# IO_MIL1553_TopConfiguration.net
KiCad netlist of a schematic drawn in Altium Designer
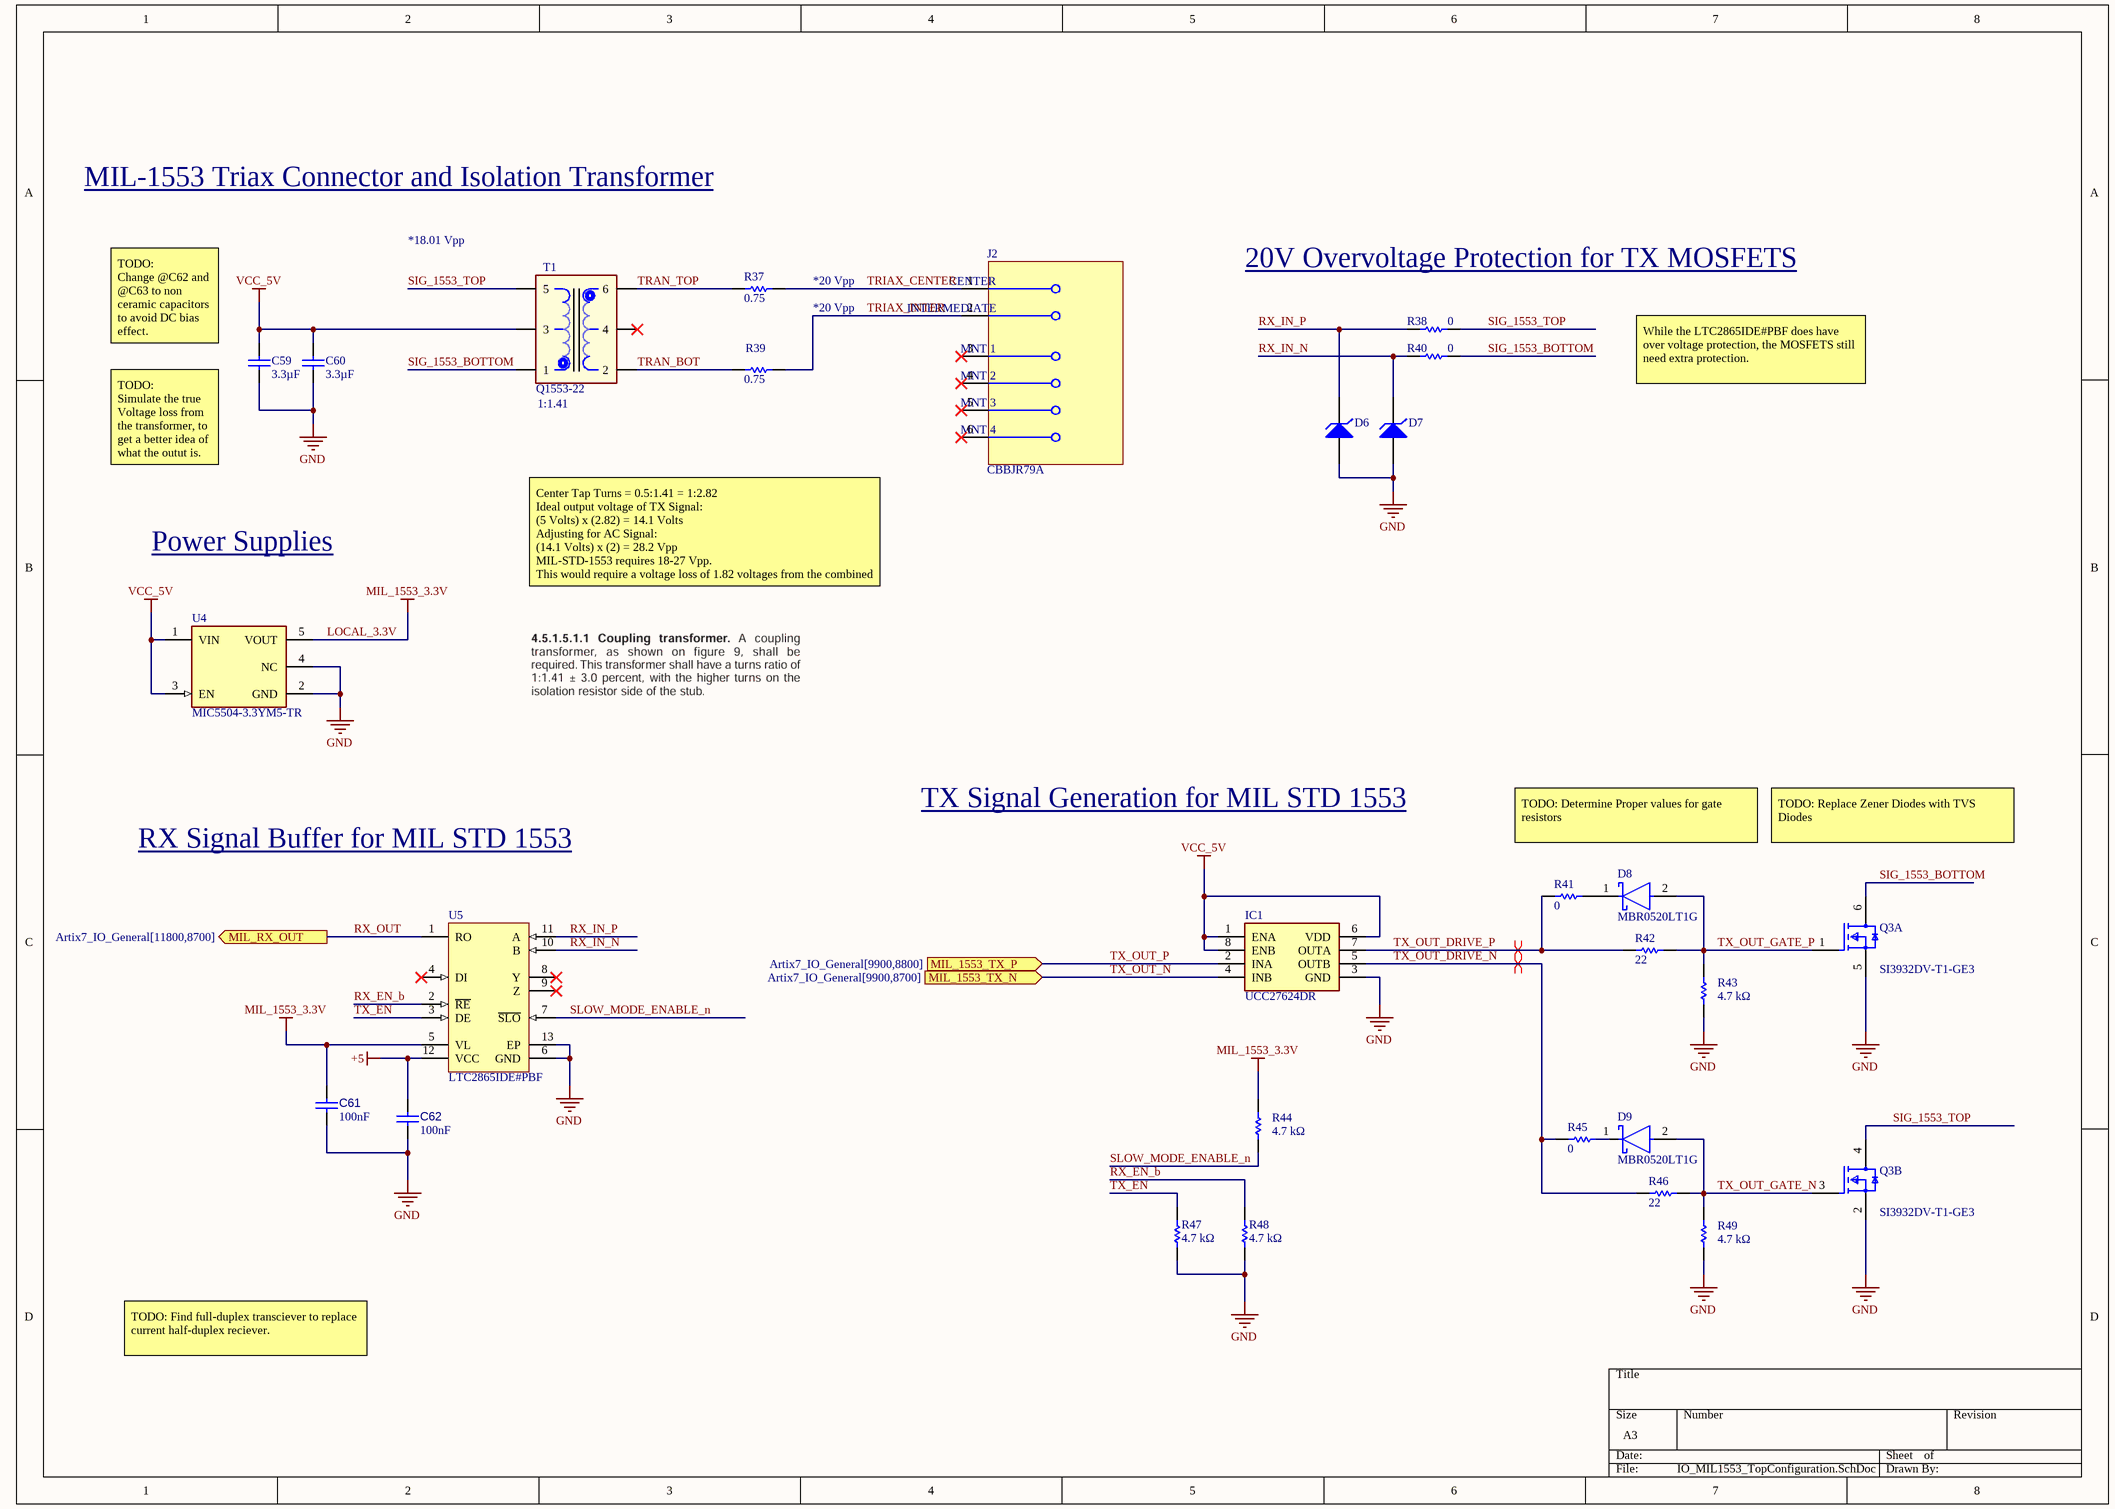
[diagram p0: IO_MIL1553_TopConfiguration.SchDoc]

(export (version "E")
  (design (tool "Eeschema 10.0.6"))
  (components
    (comp (ref "C59")
      (value "3.3µF")
      (footprint "CAPC3325X279X50NL40T25")
      (fields (field (name "Comment") "12105C335KAT2A"))
      (libsource (lib "Personal Workspace") (part "CAP-NP-2"))
    )
    (comp (ref "C60")
      (value "3.3µF")
      (footprint "CAPC3325X279X50NL40T25")
      (fields (field (name "Comment") "12105C335KAT2A"))
      (libsource (lib "Personal Workspace") (part "CAP-NP-2"))
    )
    (comp (ref "C61")
      (value "100nF")
      (footprint "CAPC2013X145X48ML20T23")
      (fields (field (name "Comment") "VJ0805Y104JXXAT"))
      (libsource (lib "Personal Workspace") (part "CAP-NP-2"))
    )
    (comp (ref "C62")
      (value "100nF")
      (footprint "CAPC2013X145X48ML20T23")
      (fields (field (name "Comment") "VJ0805Y104JXXAT"))
      (libsource (lib "Personal Workspace") (part "CAP-NP-2"))
    )
    (comp (ref "D6")
      (value "SZ1SMA5932BT3G")
      (footprint "ONSC-SMA-2-403D-02_F_V")
      (description "Zener Diode, 20V V(Z), 5%, 0.5W, Silicon, Unidirectional")
      (libsource (lib "Personal Workspace") (part "ONSC-K1A2-2"))
    )
    (comp (ref "D7")
      (value "SZ1SMA5932BT3G")
      (footprint "ONSC-SMA-2-403D-02_F_V")
      (description "Zener Diode, 20V V(Z), 5%, 0.5W, Silicon, Unidirectional")
      (libsource (lib "Personal Workspace") (part "ONSC-K1A2-2"))
    )
    (comp (ref "D8")
      (value "MBR0520LT1G")
      (footprint "FP-425-04-IPC_A")
      (description "Rectifier Diode, Schottky, 1 Phase, 1 Element, 0.5A, 20V V(RRM), Silicon")
      (libsource (lib "Personal Workspace") (part "1d6ec82d83fb6aee721767c19dac4b9"))
    )
    (comp (ref "D9")
      (value "MBR0520LT1G")
      (footprint "FP-425-04-IPC_A")
      (description "Rectifier Diode, Schottky, 1 Phase, 1 Element, 0.5A, 20V V(RRM), Silicon")
      (libsource (lib "Personal Workspace") (part "1d6ec82d83fb6aee721767c19dac4b9"))
    )
    (comp (ref "IC1")
      (value "UCC27624DR")
      (footprint "SamacSys:SOIC127P600X175-8N")
      (description "Integrated Circuit")
      (fields (field (name "MOUSER PART NUMBER") "595-UCC27624DR"))
      (libsource (lib "*") (part "UCC27624DR"))
    )
    (comp (ref "J2")
      (value "CBBJR79A")
      (footprint "CBBJR79A_MFG")
      (description "RF Triaxial-BNC Connector, Female, Panel Mount, Board And Panel Mount, Solder Terminal, Jack")
      (libsource (lib "Altium Content Vault") (part "f0f2aa2fa52ada01177f191ae970a7c"))
    )
    (comp (ref "Q3")
      (value "SI3932DV-T1-GE3")
      (footprint "FP-C-06593-6-IPC_B")
      (libsource (lib "Personal Workspace") (part "c257f011501cba683afc6ad259169fc"))
    )
    (comp (ref "R37")
      (value "0.75")
      (footprint "RESC3125X70X40LL20T20")
      (fields
        (field (name "POWER") "1W")
        (field (name "TOLERANCE") "1%")
        (field (name "Comment") "RES_0.75ohm_1W _1210")
      )
      (libsource (lib "Personal Workspace") (part "RES-2"))
    )
    (comp (ref "R38")
      (value "0")
      (footprint "RESC1608X55X25ML10T15")
      (description "Chip Resistor, 0 Ohm, 0.1 W, -55 to 155 degC, 0603 (1608 Metric)")
      (fields (field (name "POWER") "100mW") (field (name "TOLERANCE") "5%"))
      (libsource (lib "Personal Workspace") (part "RES-2"))
    )
    (comp (ref "R39")
      (value "0.75")
      (footprint "RESC3125X70X40LL20T20")
      (fields
        (field (name "POWER") "1W")
        (field (name "TOLERANCE") "1%")
        (field (name "Comment") "RES_0.75ohm_1W _1210")
      )
      (libsource (lib "Personal Workspace") (part "RES-2"))
    )
    (comp (ref "R40")
      (value "0")
      (footprint "RESC1608X55X25ML10T15")
      (description "Chip Resistor, 0 Ohm, 0.1 W, -55 to 155 degC, 0603 (1608 Metric)")
      (fields (field (name "POWER") "100mW") (field (name "TOLERANCE") "5%"))
      (libsource (lib "Personal Workspace") (part "RES-2"))
    )
    (comp (ref "R41")
      (value "0")
      (footprint "RESC1608X55X25ML10T15")
      (description "Chip Resistor, 0 Ohm, 0.1 W, -55 to 155 degC, 0603 (1608 Metric)")
      (fields (field (name "POWER") "100mW") (field (name "TOLERANCE") "5%"))
      (libsource (lib "Personal Workspace") (part "RES-2"))
    )
    (comp (ref "R42")
      (value "22")
      (footprint "RESC1608X55X25LL10T15")
      (fields
        (field (name "TOLERANCE") "1%")
        (field (name "POWER") "100mW")
        (field (name "Comment") "RC0603FR-0722RL")
      )
      (libsource (lib "Personal Workspace") (part "RES-2"))
    )
    (comp (ref "R43")
      (value "ERJ-3EKF4701V")
      (footprint "RESC1608X55X30LL15T15")
      (fields
        (field (name "TOLERANCE") "1%")
        (field (name "POWER") "100mW")
        (field (name "RESISTANCE") "4.7 kΩ")
      )
      (libsource (lib "Personal Workspace") (part "RES-2"))
    )
    (comp (ref "R44")
      (value "ERJ-3EKF4701V")
      (footprint "RESC1608X55X30LL15T15")
      (fields
        (field (name "TOLERANCE") "1%")
        (field (name "POWER") "100mW")
        (field (name "RESISTANCE") "4.7 kΩ")
      )
      (libsource (lib "Personal Workspace") (part "RES-2"))
    )
    (comp (ref "R45")
      (value "0")
      (footprint "RESC1608X55X25ML10T15")
      (description "Chip Resistor, 0 Ohm, 0.1 W, -55 to 155 degC, 0603 (1608 Metric)")
      (fields (field (name "POWER") "100mW") (field (name "TOLERANCE") "5%"))
      (libsource (lib "Personal Workspace") (part "RES-2"))
    )
    (comp (ref "R46")
      (value "22")
      (footprint "RESC1608X55X25LL10T15")
      (fields
        (field (name "TOLERANCE") "1%")
        (field (name "POWER") "100mW")
        (field (name "Comment") "RC0603FR-0722RL")
      )
      (libsource (lib "Personal Workspace") (part "RES-2"))
    )
    (comp (ref "R47")
      (value "ERJ-3EKF4701V")
      (footprint "RESC1608X55X30LL15T15")
      (fields
        (field (name "TOLERANCE") "1%")
        (field (name "POWER") "100mW")
        (field (name "RESISTANCE") "4.7 kΩ")
      )
      (libsource (lib "Personal Workspace") (part "RES-2"))
    )
    (comp (ref "R48")
      (value "ERJ-3EKF4701V")
      (footprint "RESC1608X55X30LL15T15")
      (fields
        (field (name "TOLERANCE") "1%")
        (field (name "POWER") "100mW")
        (field (name "RESISTANCE") "4.7 kΩ")
      )
      (libsource (lib "Personal Workspace") (part "RES-2"))
    )
    (comp (ref "R49")
      (value "ERJ-3EKF4701V")
      (footprint "RESC1608X55X30LL15T15")
      (fields
        (field (name "TOLERANCE") "1%")
        (field (name "POWER") "100mW")
        (field (name "RESISTANCE") "4.7 kΩ")
      )
      (libsource (lib "Personal Workspace") (part "RES-2"))
    )
    (comp (ref "T1")
      (value "Q1553-22")
      (footprint "New footprint 1")
      (description "Pulse Transformer, GENERAL PURPOSE Application(s), 1CT:1.41CT")
      (fields (field (name "TURNS RATIO") "1:1.41"))
      (libsource (lib "Personal Workspace") (part "Copy of TFORM-4"))
    )
    (comp (ref "U4")
      (value "MIC5504-3.3YM5-TR")
      (footprint "FP-SOT23-5LD-PL-1-MFG")
      (description "IC REG LINEAR 3.3V 300MA SOT23-5")
      (libsource (lib "Altium Content Vault") (part "96048095611b4a9579e1e315950d302"))
    )
    (comp (ref "U5")
      (value "LTC2865IDE#PBF")
      (footprint "LT-DE-UE-12_V")
      (description "Line Transceiver, 1 Func, 1 Driver, 1 Rcvr, CMOS, PDSO12")
      (libsource (lib "Personal Workspace") (part "LT-LTC2865-12"))
    )
  )
  (nets
    (net (code "1") (name "+5") (class "Default")
      (node (ref "C62") (pin "2") (pinfunction "2_2") (pintype "passive"))
      (node (ref "U5") (pin "12") (pinfunction "VCC_12") (pintype "power_in"))
    )
    (net (code "2") (name "/RX_EN_b") (class "Default")
      (node (ref "R48") (pin "1") (pinfunction "1_1") (pintype "passive"))
      (node (ref "U5") (pin "2") (pinfunction "~{RE}_2") (pintype "input"))
    )
    (net (code "3") (name "/RX_IN_N") (class "Default")
      (node (ref "D7") (pin "1") (pinfunction "K_1") (pintype "passive"))
      (node (ref "R40") (pin "1") (pinfunction "1_1") (pintype "passive"))
      (node (ref "U5") (pin "10") (pinfunction "B_10") (pintype "input"))
    )
    (net (code "4") (name "/RX_IN_P") (class "Default")
      (node (ref "D6") (pin "1") (pinfunction "K_1") (pintype "passive"))
      (node (ref "R38") (pin "1") (pinfunction "1_1") (pintype "passive"))
      (node (ref "U5") (pin "11") (pinfunction "A_11") (pintype "input"))
    )
    (net (code "5") (name "/RX_OUT") (class "Default")
      (node (ref "U5") (pin "1") (pinfunction "RO_1") (pintype "tri_state"))
    )
    (net (code "6") (name "/SIG_1553_BOTTOM") (class "Default")
      (node (ref "Q3") (pin "6") (pinfunction "D1_6") (pintype "passive"))
      (node (ref "R40") (pin "2") (pinfunction "2_2") (pintype "passive"))
      (node (ref "T1") (pin "1") (pinfunction "1_1") (pintype "passive"))
    )
    (net (code "7") (name "/SIG_1553_TOP") (class "Default")
      (node (ref "Q3") (pin "4") (pinfunction "D2_4") (pintype "passive"))
      (node (ref "R38") (pin "2") (pinfunction "2_2") (pintype "passive"))
      (node (ref "T1") (pin "5") (pinfunction "5_5") (pintype "passive"))
    )
    (net (code "8") (name "/SLOW_MODE_ENABLE_n") (class "Default")
      (node (ref "R44") (pin "1") (pinfunction "1_1") (pintype "passive"))
      (node (ref "U5") (pin "7") (pinfunction "~{SLO}_7") (pintype "input"))
    )
    (net (code "9") (name "/TRAN_BOT") (class "Default")
      (node (ref "R39") (pin "1") (pinfunction "1_1") (pintype "passive"))
      (node (ref "T1") (pin "2") (pinfunction "2_2") (pintype "passive"))
    )
    (net (code "10") (name "/TRAN_TOP") (class "Default")
      (node (ref "R37") (pin "1") (pinfunction "1_1") (pintype "passive"))
      (node (ref "T1") (pin "6") (pinfunction "6_6") (pintype "passive"))
    )
    (net (code "11") (name "/TRIAX_CENTER") (class "Default")
      (node (ref "J2") (pin "1") (pinfunction "CENTER_1") (pintype "passive"))
      (node (ref "R37") (pin "2") (pinfunction "2_2") (pintype "passive"))
    )
    (net (code "12") (name "/TRIAX_INTER") (class "Default")
      (node (ref "J2") (pin "2") (pinfunction "INTERMEDIATE_2") (pintype "passive"))
      (node (ref "R39") (pin "2") (pinfunction "2_2") (pintype "passive"))
    )
    (net (code "13") (name "/TX_EN") (class "Default")
      (node (ref "R47") (pin "2") (pinfunction "2_2") (pintype "passive"))
      (node (ref "U5") (pin "3") (pinfunction "DE_3") (pintype "input"))
    )
    (net (code "14") (name "/TX_OUT_DRIVE_N") (class "Default")
      (node (ref "IC1") (pin "5") (pinfunction "OUTB_5") (pintype "passive"))
      (node (ref "R45") (pin "1") (pinfunction "1_1") (pintype "passive"))
      (node (ref "R46") (pin "1") (pinfunction "1_1") (pintype "passive"))
    )
    (net (code "15") (name "/TX_OUT_DRIVE_P") (class "Default")
      (node (ref "IC1") (pin "7") (pinfunction "OUTA_7") (pintype "passive"))
      (node (ref "R41") (pin "1") (pinfunction "1_1") (pintype "passive"))
      (node (ref "R42") (pin "1") (pinfunction "1_1") (pintype "passive"))
    )
    (net (code "16") (name "/TX_OUT_GATE_N") (class "Default")
      (node (ref "D9") (pin "2") (pinfunction "A_2") (pintype "passive"))
      (node (ref "Q3") (pin "3") (pinfunction "G2_3") (pintype "passive"))
      (node (ref "R46") (pin "2") (pinfunction "2_2") (pintype "passive"))
      (node (ref "R49") (pin "2") (pinfunction "2_2") (pintype "passive"))
    )
    (net (code "17") (name "/TX_OUT_GATE_P") (class "Default")
      (node (ref "D8") (pin "2") (pinfunction "A_2") (pintype "passive"))
      (node (ref "Q3") (pin "1") (pinfunction "G1_1") (pintype "passive"))
      (node (ref "R42") (pin "2") (pinfunction "2_2") (pintype "passive"))
      (node (ref "R43") (pin "2") (pinfunction "2_2") (pintype "passive"))
    )
    (net (code "18") (name "/TX_OUT_N") (class "Default")
      (node (ref "IC1") (pin "4") (pinfunction "INB_4") (pintype "passive"))
    )
    (net (code "19") (name "/TX_OUT_P") (class "Default")
      (node (ref "IC1") (pin "2") (pinfunction "INA_2") (pintype "passive"))
    )
    (net (code "20") (name "GND") (class "Default")
      (node (ref "C59") (pin "1") (pinfunction "1_1") (pintype "passive"))
      (node (ref "C60") (pin "1") (pinfunction "1_1") (pintype "passive"))
      (node (ref "C61") (pin "1") (pinfunction "1_1") (pintype "passive"))
      (node (ref "C62") (pin "1") (pinfunction "1_1") (pintype "passive"))
      (node (ref "D6") (pin "2") (pinfunction "A_2") (pintype "passive"))
      (node (ref "D7") (pin "2") (pinfunction "A_2") (pintype "passive"))
      (node (ref "IC1") (pin "3") (pinfunction "GND_3") (pintype "passive"))
      (node (ref "Q3") (pin "2") (pinfunction "S2_2") (pintype "passive"))
      (node (ref "Q3") (pin "5") (pinfunction "S1_5") (pintype "passive"))
      (node (ref "R43") (pin "1") (pinfunction "1_1") (pintype "passive"))
      (node (ref "R47") (pin "1") (pinfunction "1_1") (pintype "passive"))
      (node (ref "R48") (pin "2") (pinfunction "2_2") (pintype "passive"))
      (node (ref "R49") (pin "1") (pinfunction "1_1") (pintype "passive"))
      (node (ref "U4") (pin "2") (pinfunction "GND_2") (pintype "power_in"))
      (node (ref "U4") (pin "4") (pinfunction "NC_4") (pintype "passive"))
      (node (ref "U5") (pin "13") (pinfunction "EP_13") (pintype "power_in"))
      (node (ref "U5") (pin "6") (pinfunction "GND_6") (pintype "power_in"))
    )
    (net (code "21") (name "MIL_1553_3.3V") (class "Default")
      (node (ref "C61") (pin "2") (pinfunction "2_2") (pintype "passive"))
      (node (ref "R44") (pin "2") (pinfunction "2_2") (pintype "passive"))
      (node (ref "U4") (pin "5") (pinfunction "VOUT_5") (pintype "power_in"))
      (node (ref "U5") (pin "5") (pinfunction "VL_5") (pintype "power_in"))
    )
    (net (code "22") (name "Net-(D8-C)") (class "Default")
      (node (ref "D8") (pin "1") (pinfunction "C_1") (pintype "passive"))
      (node (ref "R41") (pin "2") (pinfunction "2_2") (pintype "passive"))
    )
    (net (code "23") (name "Net-(D9-C)") (class "Default")
      (node (ref "D9") (pin "1") (pinfunction "C_1") (pintype "passive"))
      (node (ref "R45") (pin "2") (pinfunction "2_2") (pintype "passive"))
    )
    (net (code "24") (name "VCC_5V") (class "Default")
      (node (ref "C59") (pin "2") (pinfunction "2_2") (pintype "passive"))
      (node (ref "C60") (pin "2") (pinfunction "2_2") (pintype "passive"))
      (node (ref "IC1") (pin "1") (pinfunction "ENA_1") (pintype "passive"))
      (node (ref "IC1") (pin "6") (pinfunction "VDD_6") (pintype "passive"))
      (node (ref "IC1") (pin "8") (pinfunction "ENB_8") (pintype "passive"))
      (node (ref "T1") (pin "3") (pinfunction "3_3") (pintype "passive"))
      (node (ref "U4") (pin "1") (pinfunction "VIN_1") (pintype "power_in"))
      (node (ref "U4") (pin "3") (pinfunction "EN_3") (pintype "input"))
    )
    (net (code "25") (name "unconnected-(J2-MNT_1-Pad3)") (class "Default")
      (node (ref "J2") (pin "3") (pinfunction "MNT_1_3") (pintype "passive+no_connect"))
    )
    (net (code "26") (name "unconnected-(J2-MNT_2-Pad4)") (class "Default")
      (node (ref "J2") (pin "4") (pinfunction "MNT_2_4") (pintype "passive+no_connect"))
    )
    (net (code "27") (name "unconnected-(J2-MNT_3-Pad5)") (class "Default")
      (node (ref "J2") (pin "5") (pinfunction "MNT_3_5") (pintype "passive+no_connect"))
    )
    (net (code "28") (name "unconnected-(J2-MNT_4-Pad6)") (class "Default")
      (node (ref "J2") (pin "6") (pinfunction "MNT_4_6") (pintype "passive+no_connect"))
    )
    (net (code "29") (name "unconnected-(T1-Pad4)") (class "Default")
      (node (ref "T1") (pin "4") (pinfunction "4_4") (pintype "passive+no_connect"))
    )
    (net (code "30") (name "unconnected-(U5-DI-Pad4)") (class "Default")
      (node (ref "U5") (pin "4") (pinfunction "DI_4") (pintype "input+no_connect"))
    )
    (net (code "31") (name "unconnected-(U5-Y-Pad8)") (class "Default")
      (node (ref "U5") (pin "8") (pinfunction "Y_8") (pintype "tri_state+no_connect"))
    )
    (net (code "32") (name "unconnected-(U5-Z-Pad9)") (class "Default")
      (node (ref "U5") (pin "9") (pinfunction "Z_9") (pintype "tri_state+no_connect"))
    )
  )
)
